# design.net
KiCad netlist of a schematic drawn in Altium Designer
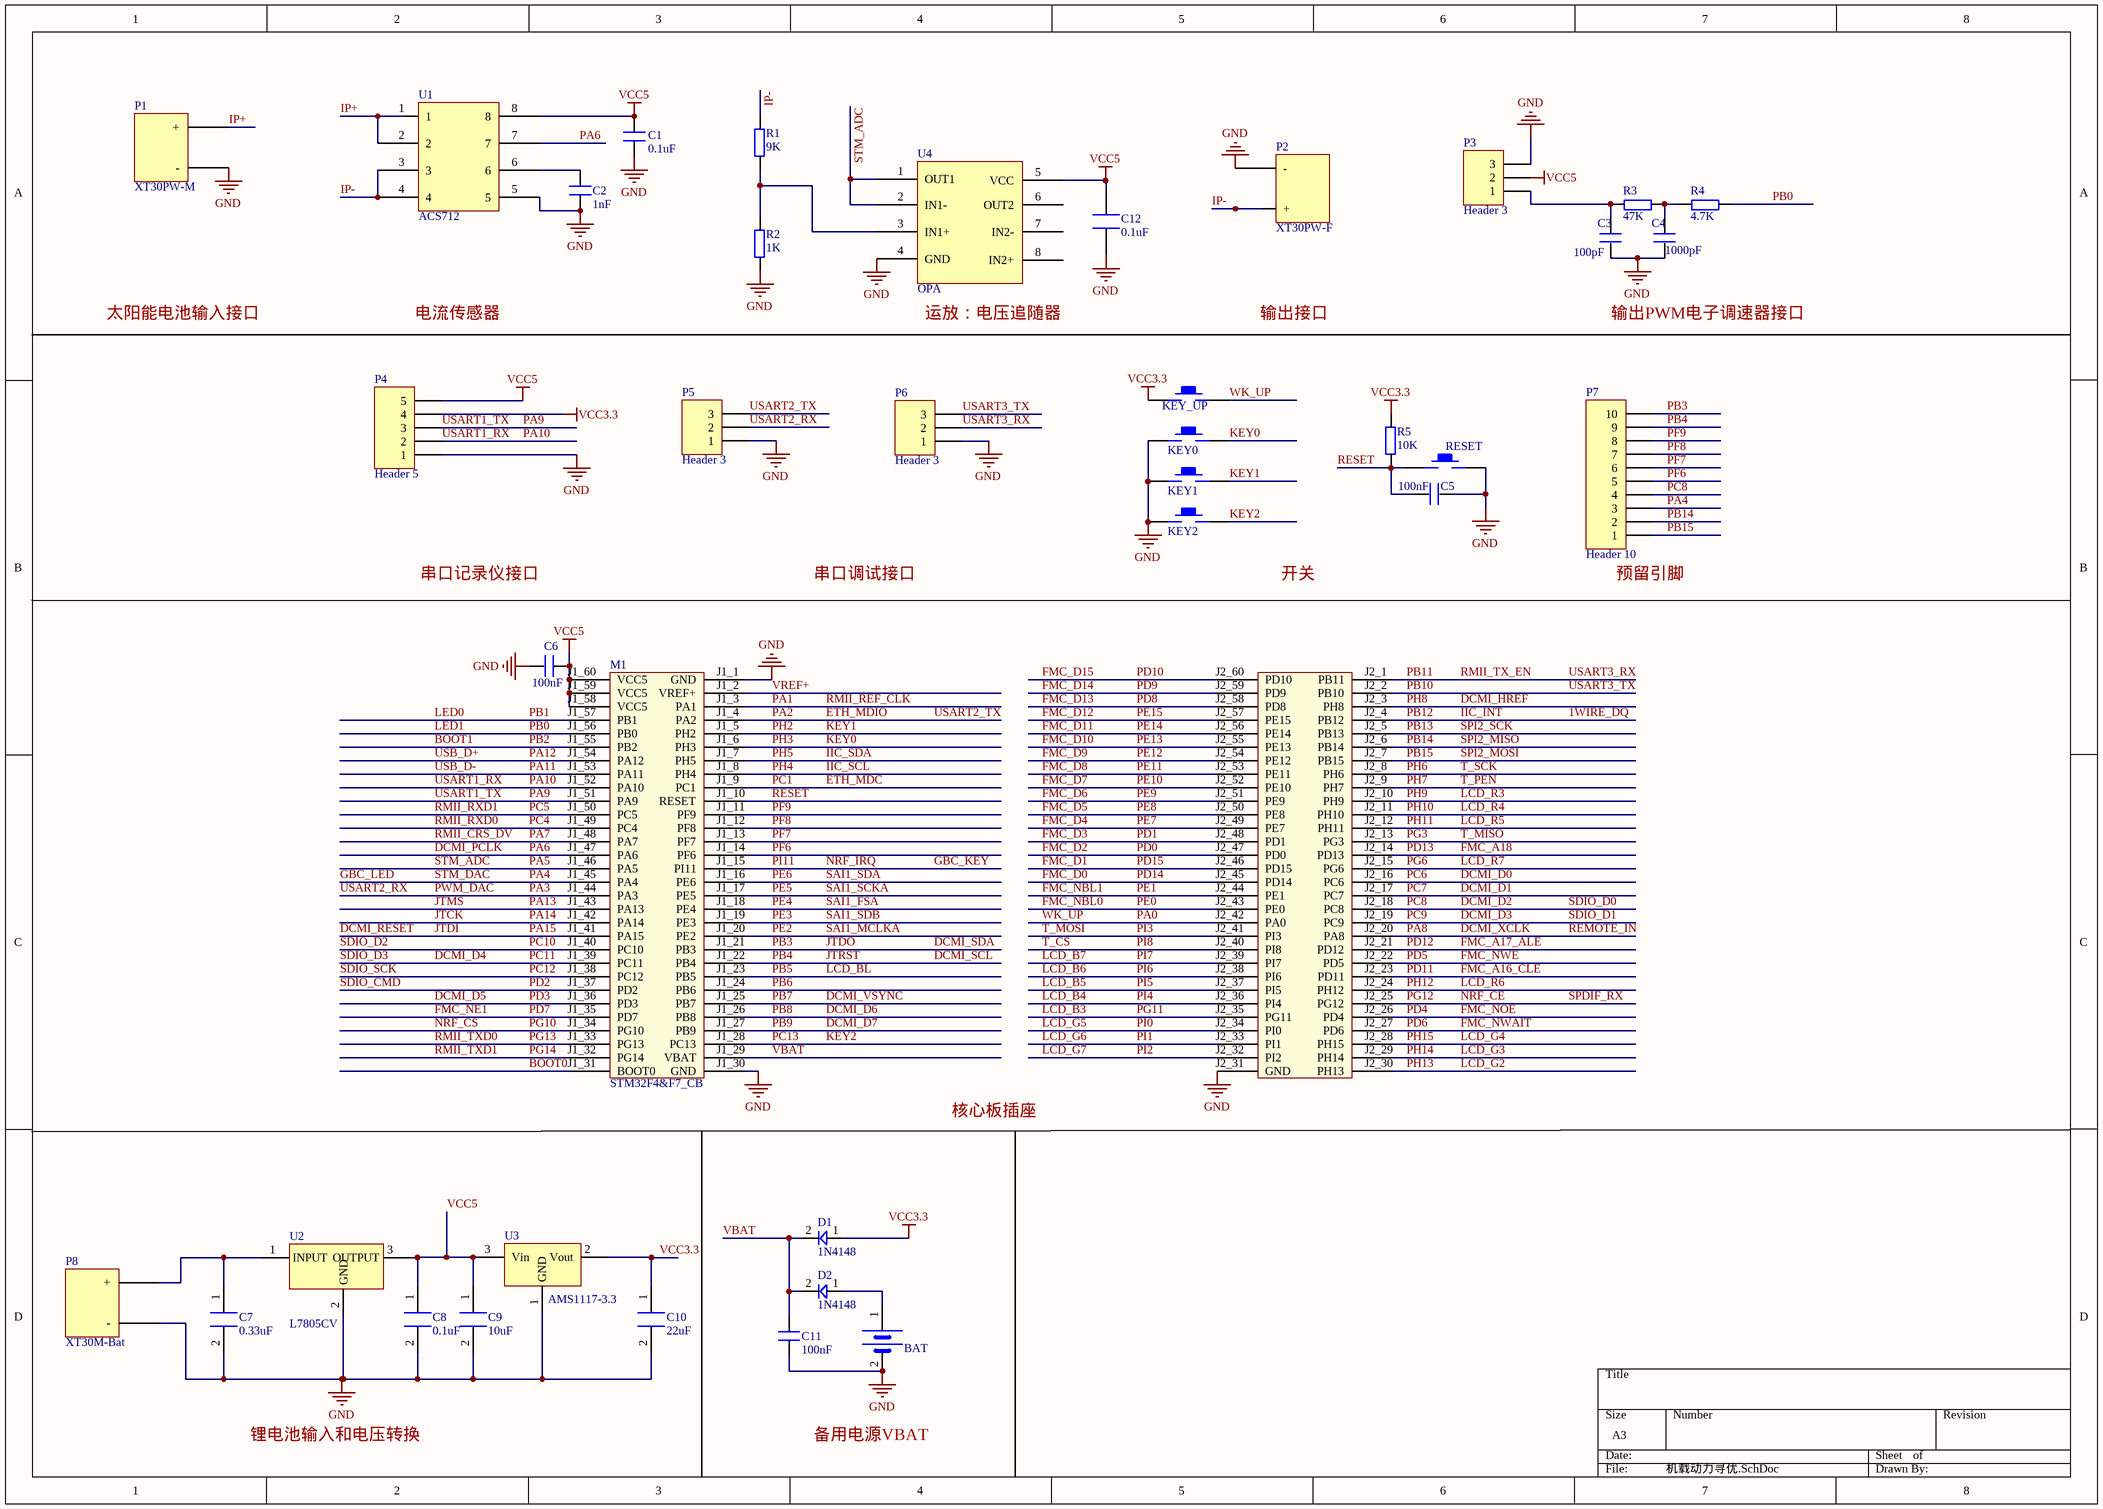
[diagram p0: 机载动力寻优.SchDoc]

(export (version "E")
  (design (tool "Eeschema 10.0.6"))
  (components
    (comp (ref "BAT")
      (value "BATT")
      (footprint "BATM")
      (description "电源")
      (libsource (lib "机载动力寻优") (part "BAT"))
    )
    (comp (ref "C1") (value "0.1uF") (footprint "0603P") (libsource (lib "STM32F429_F746") (part "C")))
    (comp (ref "C2") (value "1nF") (footprint "0603P") (libsource (lib "STM32F429_F746") (part "C")))
    (comp (ref "C3") (value "100pF") (footprint "0603P") (libsource (lib "阿波罗STM32F4&F7底板封装库") (part "C")))
    (comp (ref "C4") (value "1000pF") (footprint "0603P") (libsource (lib "阿波罗STM32F4&F7底板封装库") (part "C")))
    (comp (ref "C5") (value "100nF") (footprint "0603P") (libsource (lib "STM32F429_F746") (part "C")))
    (comp (ref "C6") (value "100nF") (footprint "0603P") (libsource (lib "STM32F429_F746") (part "C")))
    (comp (ref "C7")
      (value "0.33uF")
      (footprint "0603P")
      (description "电容")
      (libsource (lib "STM32F767") (part "CAP"))
    )
    (comp (ref "C8")
      (value "0.1uF")
      (footprint "0603P")
      (description "电容")
      (libsource (lib "STM32F767") (part "CAP"))
    )
    (comp (ref "C9")
      (value "10uF")
      (footprint "0603P")
      (description "电容")
      (libsource (lib "STM32F767") (part "CAP"))
    )
    (comp (ref "C10")
      (value "22uF")
      (footprint "0603P")
      (description "电容")
      (libsource (lib "STM32F767") (part "CAP"))
    )
    (comp (ref "C11") (value "100nF") (footprint "0603P") (libsource (lib "STM32F429_F746") (part "C")))
    (comp (ref "C12")
      (value "0.1uF")
      (footprint "0603P")
      (description "电容")
      (libsource (lib "机载动力寻优") (part "CAP"))
    )
    (comp (ref "D1")
      (value "1N4148")
      (footprint "DIODE_SOP")
      (description "二极管")
      (libsource (lib "机载动力寻优") (part "D"))
    )
    (comp (ref "D2")
      (value "1N4148")
      (footprint "DIODE_SOP")
      (description "二极管")
      (libsource (lib "机载动力寻优") (part "D"))
    )
    (comp (ref "KEY0")
      (value "KEY_M")
      (footprint "KEY_M")
      (libsource (lib "阿波罗STM32F4&F7底板封装库") (part "KEY_M"))
    )
    (comp (ref "KEY1")
      (value "KEY_M")
      (footprint "KEY_M")
      (libsource (lib "阿波罗STM32F4&F7底板封装库") (part "KEY_M"))
    )
    (comp (ref "KEY2")
      (value "KEY_M")
      (footprint "KEY_M")
      (libsource (lib "阿波罗STM32F4&F7底板封装库") (part "KEY_M"))
    )
    (comp (ref "KEY_UP")
      (value "KEY_M")
      (footprint "KEY_M")
      (libsource (lib "阿波罗STM32F4&F7底板封装库") (part "KEY_M"))
    )
    (comp (ref "M1")
      (value "STM32F4&F7_CB")
      (footprint "STM32F4&F7_CB")
      (description "F429/746 Core Board")
      (libsource (lib "STM32F429_F746") (part "STM32F4&F7_CB"))
    )
    (comp (ref "P1") (value "XT30PW-M") (footprint "XT30PW-M") (libsource (lib "Schlib1") (part "XT30PW-M")))
    (comp (ref "P2") (value "XT30PW-F") (footprint "XT30PW-F") (libsource (lib "机载动力寻优") (part "XT30PW-F")))
    (comp (ref "P3")
      (value "Header 3")
      (footprint "串口")
      (description "Header, 3-Pin")
      (fields (field (name "PUBLISHER") "Altium Limited"))
      (libsource (lib "Miscellaneous Connectors") (part "Header 3"))
    )
    (comp (ref "P4")
      (value "Header 5")
      (footprint "串口数据记录仪")
      (description "Header, 5-Pin")
      (fields (field (name "PUBLISHER") "Altium Limited"))
      (libsource (lib "Miscellaneous Connectors") (part "Header 5"))
    )
    (comp (ref "P5")
      (value "Header 3")
      (footprint "串口")
      (description "Header, 3-Pin")
      (fields (field (name "PUBLISHER") "Altium Limited"))
      (libsource (lib "Miscellaneous Connectors") (part "Header 3"))
    )
    (comp (ref "P6")
      (value "Header 3")
      (footprint "串口")
      (description "Header, 3-Pin")
      (fields (field (name "PUBLISHER") "Altium Limited"))
      (libsource (lib "Miscellaneous Connectors") (part "Header 3"))
    )
    (comp (ref "P7")
      (value "Header 10")
      (footprint "IO口")
      (description "Header, 10-Pin")
      (fields (field (name "PUBLISHER") "Altium Limited"))
      (libsource (lib "Miscellaneous Connectors") (part "Header 10"))
    )
    (comp (ref "P8")
      (value "XT30M-Bat")
      (footprint "XT30PW-M")
      (description "公头")
      (libsource (lib "机载动力寻优") (part "XT30"))
    )
    (comp (ref "R1") (value "9K") (footprint "0603P") (libsource (lib "STM32F767_CORE") (part "R")))
    (comp (ref "R2") (value "1K") (footprint "0603P") (libsource (lib "STM32F767_CORE") (part "R")))
    (comp (ref "R3") (value "47K") (footprint "0603P") (libsource (lib "阿波罗STM32F4&F7底板封装库") (part "R")))
    (comp (ref "R4") (value "4.7K") (footprint "0603P") (libsource (lib "阿波罗STM32F4&F7底板封装库") (part "R")))
    (comp (ref "R5") (value "10K") (footprint "0603P") (libsource (lib "STM32F429_F746") (part "R")))
    (comp (ref "RESET") (value "KEY_M") (footprint "KEY_M") (libsource (lib "STM32F429_F746") (part "KEY_M")))
    (comp (ref "U1") (value "ACS712") (footprint "ACS712") (libsource (lib "Schlib1") (part "ACS712")))
    (comp (ref "U2")
      (value "L7805CV")
      (footprint "TO-220-3")
      (description "IC")
      (libsource (lib "机载动力寻优") (part "L7805CV"))
    )
    (comp (ref "U3")
      (value "AMS1117-3.3")
      (footprint "SOT-223")
      (description "IC")
      (libsource (lib "机载动力寻优") (part "AMS1117-3.3"))
    )
    (comp (ref "U4")
      (value "OPA")
      (footprint "OPA")
      (description "运放器")
      (libsource (lib "机载动力寻优") (part "OPA"))
    )
  )
  (nets
    (net (code "1") (name "/1WIRE_DQ") (class "Default")
      (node (ref "M1") (pin "J2_4") (pinfunction "PB12_J2_4") (pintype "passive"))
    )
    (net (code "2") (name "/BOOT0") (class "Default")
      (node (ref "M1") (pin "J1_31") (pinfunction "BOOT0_J1_31") (pintype "passive"))
    )
    (net (code "3") (name "/BOOT1") (class "Default")
      (node (ref "M1") (pin "J1_55") (pinfunction "PB2_J1_55") (pintype "passive"))
    )
    (net (code "4") (name "/DCMI_D0") (class "Default")
      (node (ref "M1") (pin "J2_16") (pinfunction "PC6_J2_16") (pintype "passive"))
    )
    (net (code "5") (name "/DCMI_D1") (class "Default")
      (node (ref "M1") (pin "J2_17") (pinfunction "PC7_J2_17") (pintype "passive"))
    )
    (net (code "6") (name "/DCMI_D2") (class "Default")
      (node (ref "M1") (pin "J2_18") (pinfunction "PC8_J2_18") (pintype "passive"))
      (node (ref "P7") (pin "4") (pinfunction "4_4") (pintype "passive"))
    )
    (net (code "7") (name "/DCMI_D3") (class "Default")
      (node (ref "M1") (pin "J2_19") (pinfunction "PC9_J2_19") (pintype "passive"))
    )
    (net (code "8") (name "/DCMI_D4") (class "Default")
      (node (ref "M1") (pin "J1_39") (pinfunction "PC11_J1_39") (pintype "passive"))
    )
    (net (code "9") (name "/DCMI_D5") (class "Default")
      (node (ref "M1") (pin "J1_36") (pinfunction "PD3_J1_36") (pintype "passive"))
    )
    (net (code "10") (name "/DCMI_D6") (class "Default")
      (node (ref "M1") (pin "J1_26") (pinfunction "PB8_J1_26") (pintype "passive"))
    )
    (net (code "11") (name "/DCMI_D7") (class "Default")
      (node (ref "M1") (pin "J1_27") (pinfunction "PB9_J1_27") (pintype "passive"))
    )
    (net (code "12") (name "/DCMI_HREF") (class "Default")
      (node (ref "M1") (pin "J2_3") (pinfunction "PH8_J2_3") (pintype "passive"))
    )
    (net (code "13") (name "/DCMI_PCLK") (class "Default")
      (node (ref "M1") (pin "J1_47") (pinfunction "PA6_J1_47") (pintype "passive"))
      (node (ref "U1") (pin "7") (pinfunction "7_7") (pintype "passive"))
    )
    (net (code "14") (name "/DCMI_RESET") (class "Default")
      (node (ref "M1") (pin "J1_41") (pinfunction "PA15_J1_41") (pintype "passive"))
    )
    (net (code "15") (name "/DCMI_SCL") (class "Default")
      (node (ref "M1") (pin "J1_22") (pinfunction "PB4_J1_22") (pintype "passive"))
      (node (ref "P7") (pin "9") (pinfunction "9_9") (pintype "passive"))
    )
    (net (code "16") (name "/DCMI_SDA") (class "Default")
      (node (ref "M1") (pin "J1_21") (pinfunction "PB3_J1_21") (pintype "passive"))
      (node (ref "P7") (pin "10") (pinfunction "10_10") (pintype "passive"))
    )
    (net (code "17") (name "/DCMI_VSYNC") (class "Default")
      (node (ref "M1") (pin "J1_25") (pinfunction "PB7_J1_25") (pintype "passive"))
    )
    (net (code "18") (name "/DCMI_XCLK") (class "Default")
      (node (ref "M1") (pin "J2_20") (pinfunction "PA8_J2_20") (pintype "passive"))
    )
    (net (code "19") (name "/ETH_MDC") (class "Default")
      (node (ref "M1") (pin "J1_9") (pinfunction "PC1_J1_9") (pintype "passive"))
    )
    (net (code "20") (name "/ETH_MDIO") (class "Default")
      (node (ref "M1") (pin "J1_4") (pinfunction "PA2_J1_4") (pintype "passive"))
      (node (ref "P5") (pin "3") (pinfunction "3_3") (pintype "passive"))
    )
    (net (code "21") (name "/FMC_A16_CLE") (class "Default")
      (node (ref "M1") (pin "J2_23") (pinfunction "PD11_J2_23") (pintype "passive"))
    )
    (net (code "22") (name "/FMC_A17_ALE") (class "Default")
      (node (ref "M1") (pin "J2_21") (pinfunction "PD12_J2_21") (pintype "passive"))
    )
    (net (code "23") (name "/FMC_A18") (class "Default")
      (node (ref "M1") (pin "J2_14") (pinfunction "PD13_J2_14") (pintype "passive"))
    )
    (net (code "24") (name "/FMC_D0") (class "Default")
      (node (ref "M1") (pin "J2_45") (pinfunction "PD14_J2_45") (pintype "passive"))
    )
    (net (code "25") (name "/FMC_D1") (class "Default")
      (node (ref "M1") (pin "J2_46") (pinfunction "PD15_J2_46") (pintype "passive"))
    )
    (net (code "26") (name "/FMC_D2") (class "Default")
      (node (ref "M1") (pin "J2_47") (pinfunction "PD0_J2_47") (pintype "passive"))
    )
    (net (code "27") (name "/FMC_D3") (class "Default")
      (node (ref "M1") (pin "J2_48") (pinfunction "PD1_J2_48") (pintype "passive"))
    )
    (net (code "28") (name "/FMC_D4") (class "Default")
      (node (ref "M1") (pin "J2_49") (pinfunction "PE7_J2_49") (pintype "passive"))
    )
    (net (code "29") (name "/FMC_D5") (class "Default")
      (node (ref "M1") (pin "J2_50") (pinfunction "PE8_J2_50") (pintype "passive"))
    )
    (net (code "30") (name "/FMC_D6") (class "Default")
      (node (ref "M1") (pin "J2_51") (pinfunction "PE9_J2_51") (pintype "passive"))
    )
    (net (code "31") (name "/FMC_D7") (class "Default")
      (node (ref "M1") (pin "J2_52") (pinfunction "PE10_J2_52") (pintype "passive"))
    )
    (net (code "32") (name "/FMC_D8") (class "Default")
      (node (ref "M1") (pin "J2_53") (pinfunction "PE11_J2_53") (pintype "passive"))
    )
    (net (code "33") (name "/FMC_D9") (class "Default")
      (node (ref "M1") (pin "J2_54") (pinfunction "PE12_J2_54") (pintype "passive"))
    )
    (net (code "34") (name "/FMC_D10") (class "Default")
      (node (ref "M1") (pin "J2_55") (pinfunction "PE13_J2_55") (pintype "passive"))
    )
    (net (code "35") (name "/FMC_D11") (class "Default")
      (node (ref "M1") (pin "J2_56") (pinfunction "PE14_J2_56") (pintype "passive"))
    )
    (net (code "36") (name "/FMC_D12") (class "Default")
      (node (ref "M1") (pin "J2_57") (pinfunction "PE15_J2_57") (pintype "passive"))
    )
    (net (code "37") (name "/FMC_D13") (class "Default")
      (node (ref "M1") (pin "J2_58") (pinfunction "PD8_J2_58") (pintype "passive"))
    )
    (net (code "38") (name "/FMC_D14") (class "Default")
      (node (ref "M1") (pin "J2_59") (pinfunction "PD9_J2_59") (pintype "passive"))
    )
    (net (code "39") (name "/FMC_D15") (class "Default")
      (node (ref "M1") (pin "J2_60") (pinfunction "PD10_J2_60") (pintype "passive"))
    )
    (net (code "40") (name "/FMC_NBL0") (class "Default")
      (node (ref "M1") (pin "J2_43") (pinfunction "PE0_J2_43") (pintype "passive"))
    )
    (net (code "41") (name "/FMC_NBL1") (class "Default")
      (node (ref "M1") (pin "J2_44") (pinfunction "PE1_J2_44") (pintype "passive"))
    )
    (net (code "42") (name "/FMC_NE1") (class "Default")
      (node (ref "M1") (pin "J1_35") (pinfunction "PD7_J1_35") (pintype "passive"))
    )
    (net (code "43") (name "/FMC_NOE") (class "Default")
      (node (ref "M1") (pin "J2_26") (pinfunction "PD4_J2_26") (pintype "passive"))
    )
    (net (code "44") (name "/FMC_NWAIT") (class "Default")
      (node (ref "M1") (pin "J2_27") (pinfunction "PD6_J2_27") (pintype "passive"))
    )
    (net (code "45") (name "/FMC_NWE") (class "Default")
      (node (ref "M1") (pin "J2_22") (pinfunction "PD5_J2_22") (pintype "passive"))
    )
    (net (code "46") (name "/GBC_KEY") (class "Default")
      (node (ref "M1") (pin "J1_15") (pinfunction "PI11_J1_15") (pintype "passive"))
    )
    (net (code "47") (name "/GBC_LED") (class "Default")
      (node (ref "M1") (pin "J1_45") (pinfunction "PA4_J1_45") (pintype "passive"))
      (node (ref "P7") (pin "3") (pinfunction "3_3") (pintype "passive"))
    )
    (net (code "48") (name "/IIC_SCL") (class "Default")
      (node (ref "M1") (pin "J1_8") (pinfunction "PH4_J1_8") (pintype "passive"))
    )
    (net (code "49") (name "/IIC_SDA") (class "Default")
      (node (ref "M1") (pin "J1_7") (pinfunction "PH5_J1_7") (pintype "passive"))
    )
    (net (code "50") (name "/IP+") (class "Default")
      (node (ref "P1") (pin "1") (pinfunction "+_1") (pintype "passive"))
      (node (ref "U1") (pin "1") (pinfunction "1_1") (pintype "passive"))
      (node (ref "U1") (pin "2") (pinfunction "2_2") (pintype "passive"))
    )
    (net (code "51") (name "/IP-") (class "Default")
      (node (ref "P2") (pin "1") (pinfunction "+_1") (pintype "passive"))
      (node (ref "R1") (pin "1") (pintype "passive"))
      (node (ref "U1") (pin "3") (pinfunction "3_3") (pintype "passive"))
      (node (ref "U1") (pin "4") (pinfunction "4_4") (pintype "passive"))
    )
    (net (code "52") (name "/JTCK") (class "Default")
      (node (ref "M1") (pin "J1_42") (pinfunction "PA14_J1_42") (pintype "passive"))
    )
    (net (code "53") (name "/JTMS") (class "Default")
      (node (ref "M1") (pin "J1_43") (pinfunction "PA13_J1_43") (pintype "passive"))
    )
    (net (code "54") (name "/KEY0") (class "Default")
      (node (ref "KEY0") (pin "2") (pinfunction "2_2") (pintype "passive"))
      (node (ref "M1") (pin "J1_6") (pinfunction "PH3_J1_6") (pintype "passive"))
    )
    (net (code "55") (name "/KEY1") (class "Default")
      (node (ref "KEY1") (pin "2") (pinfunction "2_2") (pintype "passive"))
      (node (ref "M1") (pin "J1_5") (pinfunction "PH2_J1_5") (pintype "passive"))
    )
    (net (code "56") (name "/KEY2") (class "Default")
      (node (ref "KEY2") (pin "2") (pinfunction "2_2") (pintype "passive"))
      (node (ref "M1") (pin "J1_28") (pinfunction "PC13_J1_28") (pintype "passive"))
    )
    (net (code "57") (name "/LCD_B3") (class "Default")
      (node (ref "M1") (pin "J2_35") (pinfunction "PG11_J2_35") (pintype "passive"))
    )
    (net (code "58") (name "/LCD_B4") (class "Default")
      (node (ref "M1") (pin "J2_36") (pinfunction "PI4_J2_36") (pintype "passive"))
    )
    (net (code "59") (name "/LCD_B5") (class "Default")
      (node (ref "M1") (pin "J2_37") (pinfunction "PI5_J2_37") (pintype "passive"))
    )
    (net (code "60") (name "/LCD_B6") (class "Default")
      (node (ref "M1") (pin "J2_38") (pinfunction "PI6_J2_38") (pintype "passive"))
    )
    (net (code "61") (name "/LCD_B7") (class "Default")
      (node (ref "M1") (pin "J2_39") (pinfunction "PI7_J2_39") (pintype "passive"))
    )
    (net (code "62") (name "/LCD_BL") (class "Default")
      (node (ref "M1") (pin "J1_23") (pinfunction "PB5_J1_23") (pintype "passive"))
    )
    (net (code "63") (name "/LCD_G2") (class "Default")
      (node (ref "M1") (pin "J2_30") (pinfunction "PH13_J2_30") (pintype "passive"))
    )
    (net (code "64") (name "/LCD_G3") (class "Default")
      (node (ref "M1") (pin "J2_29") (pinfunction "PH14_J2_29") (pintype "passive"))
    )
    (net (code "65") (name "/LCD_G4") (class "Default")
      (node (ref "M1") (pin "J2_28") (pinfunction "PH15_J2_28") (pintype "passive"))
    )
    (net (code "66") (name "/LCD_G5") (class "Default")
      (node (ref "M1") (pin "J2_34") (pinfunction "PI0_J2_34") (pintype "passive"))
    )
    (net (code "67") (name "/LCD_G6") (class "Default")
      (node (ref "M1") (pin "J2_33") (pinfunction "PI1_J2_33") (pintype "passive"))
    )
    (net (code "68") (name "/LCD_G7") (class "Default")
      (node (ref "M1") (pin "J2_32") (pinfunction "PI2_J2_32") (pintype "passive"))
    )
    (net (code "69") (name "/LCD_R3") (class "Default")
      (node (ref "M1") (pin "J2_10") (pinfunction "PH9_J2_10") (pintype "passive"))
    )
    (net (code "70") (name "/LCD_R4") (class "Default")
      (node (ref "M1") (pin "J2_11") (pinfunction "PH10_J2_11") (pintype "passive"))
    )
    (net (code "71") (name "/LCD_R5") (class "Default")
      (node (ref "M1") (pin "J2_12") (pinfunction "PH11_J2_12") (pintype "passive"))
    )
    (net (code "72") (name "/LCD_R6") (class "Default")
      (node (ref "M1") (pin "J2_24") (pinfunction "PH12_J2_24") (pintype "passive"))
    )
    (net (code "73") (name "/LCD_R7") (class "Default")
      (node (ref "M1") (pin "J2_15") (pinfunction "PG6_J2_15") (pintype "passive"))
    )
    (net (code "74") (name "/LED0") (class "Default")
      (node (ref "M1") (pin "J1_57") (pinfunction "PB1_J1_57") (pintype "passive"))
    )
    (net (code "75") (name "/LED1") (class "Default")
      (node (ref "M1") (pin "J1_56") (pinfunction "PB0_J1_56") (pintype "passive"))
      (node (ref "R4") (pin "2") (pintype "passive"))
    )
    (net (code "76") (name "/NRF_CE") (class "Default")
      (node (ref "M1") (pin "J2_25") (pinfunction "PG12_J2_25") (pintype "passive"))
    )
    (net (code "77") (name "/NRF_CS") (class "Default")
      (node (ref "M1") (pin "J1_34") (pinfunction "PG10_J1_34") (pintype "passive"))
    )
    (net (code "78") (name "/PA0") (class "Default")
      (node (ref "KEY_UP") (pin "2") (pinfunction "2_2") (pintype "passive"))
      (node (ref "M1") (pin "J2_42") (pinfunction "PA0_J2_42") (pintype "passive"))
    )
    (net (code "79") (name "/PA1") (class "Default")
      (node (ref "M1") (pin "J1_3") (pinfunction "PA1_J1_3") (pintype "passive"))
    )
    (net (code "80") (name "/PA3") (class "Default")
      (node (ref "M1") (pin "J1_44") (pinfunction "PA3_J1_44") (pintype "passive"))
      (node (ref "P5") (pin "2") (pinfunction "2_2") (pintype "passive"))
    )
    (net (code "81") (name "/PA5") (class "Default")
      (node (ref "M1") (pin "J1_46") (pinfunction "PA5_J1_46") (pintype "passive"))
      (node (ref "U4") (pin "1") (pinfunction "OUT1_1") (pintype "passive"))
      (node (ref "U4") (pin "2") (pinfunction "IN1-_2") (pintype "passive"))
    )
    (net (code "82") (name "/PA7") (class "Default")
      (node (ref "M1") (pin "J1_48") (pinfunction "PA7_J1_48") (pintype "passive"))
    )
    (net (code "83") (name "/PA9") (class "Default")
      (node (ref "M1") (pin "J1_51") (pinfunction "PA9_J1_51") (pintype "passive"))
      (node (ref "P4") (pin "3") (pinfunction "3_3") (pintype "passive"))
    )
    (net (code "84") (name "/PA10") (class "Default")
      (node (ref "M1") (pin "J1_52") (pinfunction "PA10_J1_52") (pintype "passive"))
      (node (ref "P4") (pin "2") (pinfunction "2_2") (pintype "passive"))
    )
    (net (code "85") (name "/PA11") (class "Default")
      (node (ref "M1") (pin "J1_53") (pinfunction "PA11_J1_53") (pintype "passive"))
    )
    (net (code "86") (name "/PA12") (class "Default")
      (node (ref "M1") (pin "J1_54") (pinfunction "PA12_J1_54") (pintype "passive"))
    )
    (net (code "87") (name "/PB6") (class "Default")
      (node (ref "M1") (pin "J1_24") (pinfunction "PB6_J1_24") (pintype "passive"))
    )
    (net (code "88") (name "/PB10") (class "Default")
      (node (ref "M1") (pin "J2_2") (pinfunction "PB10_J2_2") (pintype "passive"))
      (node (ref "P6") (pin "3") (pinfunction "3_3") (pintype "passive"))
    )
    (net (code "89") (name "/PB11") (class "Default")
      (node (ref "M1") (pin "J2_1") (pinfunction "PB11_J2_1") (pintype "passive"))
      (node (ref "P6") (pin "2") (pinfunction "2_2") (pintype "passive"))
    )
    (net (code "90") (name "/PB13") (class "Default")
      (node (ref "M1") (pin "J2_5") (pinfunction "PB13_J2_5") (pintype "passive"))
    )
    (net (code "91") (name "/PB14") (class "Default")
      (node (ref "M1") (pin "J2_6") (pinfunction "PB14_J2_6") (pintype "passive"))
      (node (ref "P7") (pin "2") (pinfunction "2_2") (pintype "passive"))
    )
    (net (code "92") (name "/PB15") (class "Default")
      (node (ref "M1") (pin "J2_7") (pinfunction "PB15_J2_7") (pintype "passive"))
      (node (ref "P7") (pin "1") (pinfunction "1_1") (pintype "passive"))
    )
    (net (code "93") (name "/PC4") (class "Default")
      (node (ref "M1") (pin "J1_49") (pinfunction "PC4_J1_49") (pintype "passive"))
    )
    (net (code "94") (name "/PC5") (class "Default")
      (node (ref "M1") (pin "J1_50") (pinfunction "PC5_J1_50") (pintype "passive"))
    )
    (net (code "95") (name "/PC10") (class "Default")
      (node (ref "M1") (pin "J1_40") (pinfunction "PC10_J1_40") (pintype "passive"))
    )
    (net (code "96") (name "/PC12") (class "Default")
      (node (ref "M1") (pin "J1_38") (pinfunction "PC12_J1_38") (pintype "passive"))
    )
    (net (code "97") (name "/PD2") (class "Default")
      (node (ref "M1") (pin "J1_37") (pinfunction "PD2_J1_37") (pintype "passive"))
    )
    (net (code "98") (name "/PE2") (class "Default")
      (node (ref "M1") (pin "J1_20") (pinfunction "PE2_J1_20") (pintype "passive"))
    )
    (net (code "99") (name "/PE3") (class "Default")
      (node (ref "M1") (pin "J1_19") (pinfunction "PE3_J1_19") (pintype "passive"))
    )
    (net (code "100") (name "/PE4") (class "Default")
      (node (ref "M1") (pin "J1_18") (pinfunction "PE4_J1_18") (pintype "passive"))
    )
    (net (code "101") (name "/PE5") (class "Default")
      (node (ref "M1") (pin "J1_17") (pinfunction "PE5_J1_17") (pintype "passive"))
    )
    (net (code "102") (name "/PE6") (class "Default")
      (node (ref "M1") (pin "J1_16") (pinfunction "PE6_J1_16") (pintype "passive"))
    )
    (net (code "103") (name "/PF6") (class "Default")
      (node (ref "M1") (pin "J1_14") (pinfunction "PF6_J1_14") (pintype "passive"))
      (node (ref "P7") (pin "5") (pinfunction "5_5") (pintype "passive"))
    )
    (net (code "104") (name "/PF7") (class "Default")
      (node (ref "M1") (pin "J1_13") (pinfunction "PF7_J1_13") (pintype "passive"))
      (node (ref "P7") (pin "6") (pinfunction "6_6") (pintype "passive"))
    )
    (net (code "105") (name "/PF8") (class "Default")
      (node (ref "M1") (pin "J1_12") (pinfunction "PF8_J1_12") (pintype "passive"))
      (node (ref "P7") (pin "7") (pinfunction "7_7") (pintype "passive"))
    )
    (net (code "106") (name "/PF9") (class "Default")
      (node (ref "M1") (pin "J1_11") (pinfunction "PF9_J1_11") (pintype "passive"))
      (node (ref "P7") (pin "8") (pinfunction "8_8") (pintype "passive"))
    )
    (net (code "107") (name "/PG3") (class "Default")
      (node (ref "M1") (pin "J2_13") (pinfunction "PG3_J2_13") (pintype "passive"))
    )
    (net (code "108") (name "/PG13") (class "Default")
      (node (ref "M1") (pin "J1_33") (pinfunction "PG13_J1_33") (pintype "passive"))
    )
    (net (code "109") (name "/PG14") (class "Default")
      (node (ref "M1") (pin "J1_32") (pinfunction "PG14_J1_32") (pintype "passive"))
    )
    (net (code "110") (name "/PH6") (class "Default")
      (node (ref "M1") (pin "J2_8") (pinfunction "PH6_J2_8") (pintype "passive"))
    )
    (net (code "111") (name "/PH7") (class "Default")
      (node (ref "M1") (pin "J2_9") (pinfunction "PH7_J2_9") (pintype "passive"))
    )
    (net (code "112") (name "/PI3") (class "Default")
      (node (ref "M1") (pin "J2_41") (pinfunction "PI3_J2_41") (pintype "passive"))
    )
    (net (code "113") (name "/PI8") (class "Default")
      (node (ref "M1") (pin "J2_40") (pinfunction "PI8_J2_40") (pintype "passive"))
    )
    (net (code "114") (name "/RESET") (class "Default")
      (node (ref "C5") (pin "1") (pintype "passive"))
      (node (ref "M1") (pin "J1_10") (pinfunction "RESET_J1_10") (pintype "passive"))
      (node (ref "R5") (pin "2") (pintype "passive"))
      (node (ref "RESET") (pin "1") (pinfunction "1_1") (pintype "passive"))
    )
    (net (code "115") (name "/VBAT") (class "Default")
      (node (ref "C11") (pin "2") (pintype "passive"))
      (node (ref "D1") (pin "2") (pintype "passive"))
      (node (ref "D2") (pin "2") (pintype "passive"))
      (node (ref "M1") (pin "J1_29") (pinfunction "VBAT_J1_29") (pintype "passive"))
    )
    (net (code "116") (name "/VREF+") (class "Default")
      (node (ref "M1") (pin "J1_2") (pinfunction "VREF+_J1_2") (pintype "passive"))
    )
    (net (code "117") (name "GND") (class "Default")
      (node (ref "BAT") (pin "2") (pinfunction "GND_2") (pintype "passive"))
      (node (ref "C1") (pin "1") (pintype "passive"))
      (node (ref "C10") (pin "2") (pinfunction "2_2") (pintype "passive"))
      (node (ref "C11") (pin "1") (pintype "passive"))
      (node (ref "C12") (pin "1") (pinfunction "1_1") (pintype "passive"))
      (node (ref "C2") (pin "1") (pintype "passive"))
      (node (ref "C3") (pin "1") (pintype "passive"))
      (node (ref "C4") (pin "1") (pintype "passive"))
      (node (ref "C5") (pin "2") (pintype "passive"))
      (node (ref "C6") (pin "1") (pintype "passive"))
      (node (ref "C7") (pin "2") (pinfunction "2_2") (pintype "passive"))
      (node (ref "C8") (pin "2") (pinfunction "2_2") (pintype "passive"))
      (node (ref "C9") (pin "2") (pinfunction "2_2") (pintype "passive"))
      (node (ref "KEY0") (pin "1") (pinfunction "1_1") (pintype "passive"))
      (node (ref "KEY1") (pin "1") (pinfunction "1_1") (pintype "passive"))
      (node (ref "KEY2") (pin "1") (pinfunction "1_1") (pintype "passive"))
      (node (ref "M1") (pin "J1_1") (pinfunction "GND_J1_1") (pintype "passive"))
      (node (ref "M1") (pin "J1_30") (pinfunction "GND_J1_30") (pintype "passive"))
      (node (ref "M1") (pin "J2_31") (pinfunction "GND_J2_31") (pintype "passive"))
      (node (ref "P1") (pin "2") (pinfunction "-_2") (pintype "passive"))
      (node (ref "P2") (pin "2") (pinfunction "-_2") (pintype "passive"))
      (node (ref "P3") (pin "3") (pinfunction "3_3") (pintype "passive"))
      (node (ref "P4") (pin "1") (pinfunction "1_1") (pintype "passive"))
      (node (ref "P5") (pin "1") (pinfunction "1_1") (pintype "passive"))
      (node (ref "P6") (pin "1") (pinfunction "1_1") (pintype "passive"))
      (node (ref "P8") (pin "2") (pinfunction "-_2") (pintype "passive"))
      (node (ref "R2") (pin "2") (pintype "passive"))
      (node (ref "RESET") (pin "2") (pinfunction "2_2") (pintype "passive"))
      (node (ref "U1") (pin "5") (pinfunction "5_5") (pintype "passive"))
      (node (ref "U2") (pin "2") (pinfunction "GND_2") (pintype "passive"))
      (node (ref "U3") (pin "1") (pinfunction "GND_1") (pintype "passive"))
      (node (ref "U4") (pin "4") (pinfunction "GND_4") (pintype "passive"))
    )
    (net (code "118") (name "Net-(BAT-VCC)") (class "Default")
      (node (ref "BAT") (pin "1") (pinfunction "VCC_1") (pintype "passive"))
      (node (ref "D2") (pin "1") (pintype "passive"))
    )
    (net (code "119") (name "Net-(C2-Pad2)") (class "Default")
      (node (ref "C2") (pin "2") (pintype "passive"))
      (node (ref "U1") (pin "6") (pinfunction "6_6") (pintype "passive"))
    )
    (net (code "120") (name "Net-(C3-Pad2)") (class "Default")
      (node (ref "C3") (pin "2") (pintype "passive"))
      (node (ref "P3") (pin "1") (pinfunction "1_1") (pintype "passive"))
      (node (ref "R3") (pin "1") (pintype "passive"))
    )
    (net (code "121") (name "Net-(C4-Pad2)") (class "Default")
      (node (ref "C4") (pin "2") (pintype "passive"))
      (node (ref "R3") (pin "2") (pintype "passive"))
      (node (ref "R4") (pin "1") (pintype "passive"))
    )
    (net (code "122") (name "Net-(P8-+)") (class "Default")
      (node (ref "C7") (pin "1") (pinfunction "1_1") (pintype "passive"))
      (node (ref "P8") (pin "1") (pinfunction "+_1") (pintype "passive"))
      (node (ref "U2") (pin "1") (pinfunction "INPUT_1") (pintype "passive"))
    )
    (net (code "123") (name "Net-(U4-IN1+)") (class "Default")
      (node (ref "R1") (pin "2") (pintype "passive"))
      (node (ref "R2") (pin "1") (pintype "passive"))
      (node (ref "U4") (pin "3") (pinfunction "IN1+_3") (pintype "passive"))
    )
    (net (code "124") (name "VCC3.3") (class "Default")
      (node (ref "C10") (pin "1") (pinfunction "1_1") (pintype "passive"))
      (node (ref "D1") (pin "1") (pintype "passive"))
      (node (ref "KEY_UP") (pin "1") (pinfunction "1_1") (pintype "passive"))
      (node (ref "P4") (pin "4") (pinfunction "4_4") (pintype "passive"))
      (node (ref "R5") (pin "1") (pintype "passive"))
      (node (ref "U3") (pin "2") (pinfunction "Vout_2") (pintype "passive"))
    )
    (net (code "125") (name "VCC5") (class "Default")
      (node (ref "C1") (pin "2") (pintype "passive"))
      (node (ref "C12") (pin "2") (pinfunction "2_2") (pintype "passive"))
      (node (ref "C6") (pin "2") (pintype "passive"))
      (node (ref "C8") (pin "1") (pinfunction "1_1") (pintype "passive"))
      (node (ref "C9") (pin "1") (pinfunction "1_1") (pintype "passive"))
      (node (ref "M1") (pin "J1_58") (pinfunction "VCC5_J1_58") (pintype "passive"))
      (node (ref "M1") (pin "J1_59") (pinfunction "VCC5_J1_59") (pintype "passive"))
      (node (ref "M1") (pin "J1_60") (pinfunction "VCC5_J1_60") (pintype "passive"))
      (node (ref "P3") (pin "2") (pinfunction "2_2") (pintype "passive"))
      (node (ref "P4") (pin "5") (pinfunction "5_5") (pintype "passive"))
      (node (ref "U1") (pin "8") (pinfunction "8_8") (pintype "passive"))
      (node (ref "U2") (pin "3") (pinfunction "OUTPUT_3") (pintype "passive"))
      (node (ref "U3") (pin "3") (pinfunction "Vin_3") (pintype "passive"))
      (node (ref "U4") (pin "5") (pinfunction "VCC_5") (pintype "passive"))
    )
    (net (code "126") (name "unconnected-(U4-IN2+-Pad8)") (class "Default")
      (node (ref "U4") (pin "8") (pinfunction "IN2+_8") (pintype "passive"))
    )
    (net (code "127") (name "unconnected-(U4-IN2--Pad7)") (class "Default")
      (node (ref "U4") (pin "7") (pinfunction "IN2-_7") (pintype "passive"))
    )
    (net (code "128") (name "unconnected-(U4-OUT2-Pad6)") (class "Default")
      (node (ref "U4") (pin "6") (pinfunction "OUT2_6") (pintype "passive"))
    )
  )
)
